# Ult_Sonic_main.net
KiCad netlist of a schematic drawn in Altium Designer
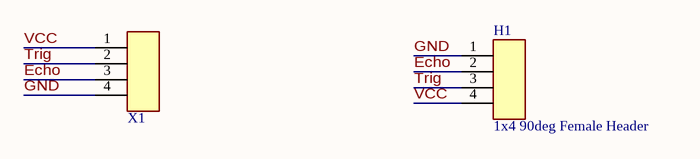
[diagram p0: Ult_Sonic_main.SchDoc]

(export (version "E")
  (design (tool "Eeschema 10.0.6"))
  (components
    (comp (ref "H1")
      (value "1x4 90deg Female Header")
      (footprint "[Header] 1x4 90deg female")
      (description "2.54mm pitch")
      (libsource (lib "Connectors") (part "[Header] 1x4 90deg Female"))
    )
    (comp (ref "X1")
      (value "[Sherlock] 90 deg 4pin")
      (footprint "[Sherlock] 90deg 4pin")
      (description "0353620450")
      (libsource (lib "Connectors") (part "[Sherlock] 90 deg 4pin"))
    )
  )
  (nets
    (net (code "1") (name "/Echo") (class "Default")
      (node (ref "H1") (pin "2") (pintype "passive"))
      (node (ref "X1") (pin "3") (pintype "passive"))
    )
    (net (code "2") (name "/GND") (class "Default")
      (node (ref "H1") (pin "1") (pintype "passive"))
      (node (ref "X1") (pin "4") (pintype "passive"))
    )
    (net (code "3") (name "/Trig") (class "Default")
      (node (ref "H1") (pin "3") (pintype "passive"))
      (node (ref "X1") (pin "2") (pintype "passive"))
    )
    (net (code "4") (name "/VCC") (class "Default")
      (node (ref "H1") (pin "4") (pintype "passive"))
      (node (ref "X1") (pin "1") (pintype "passive"))
    )
  )
)
